# aw_801_oscilloscope.net
KiCad netlist of a schematic drawn in EAGLE
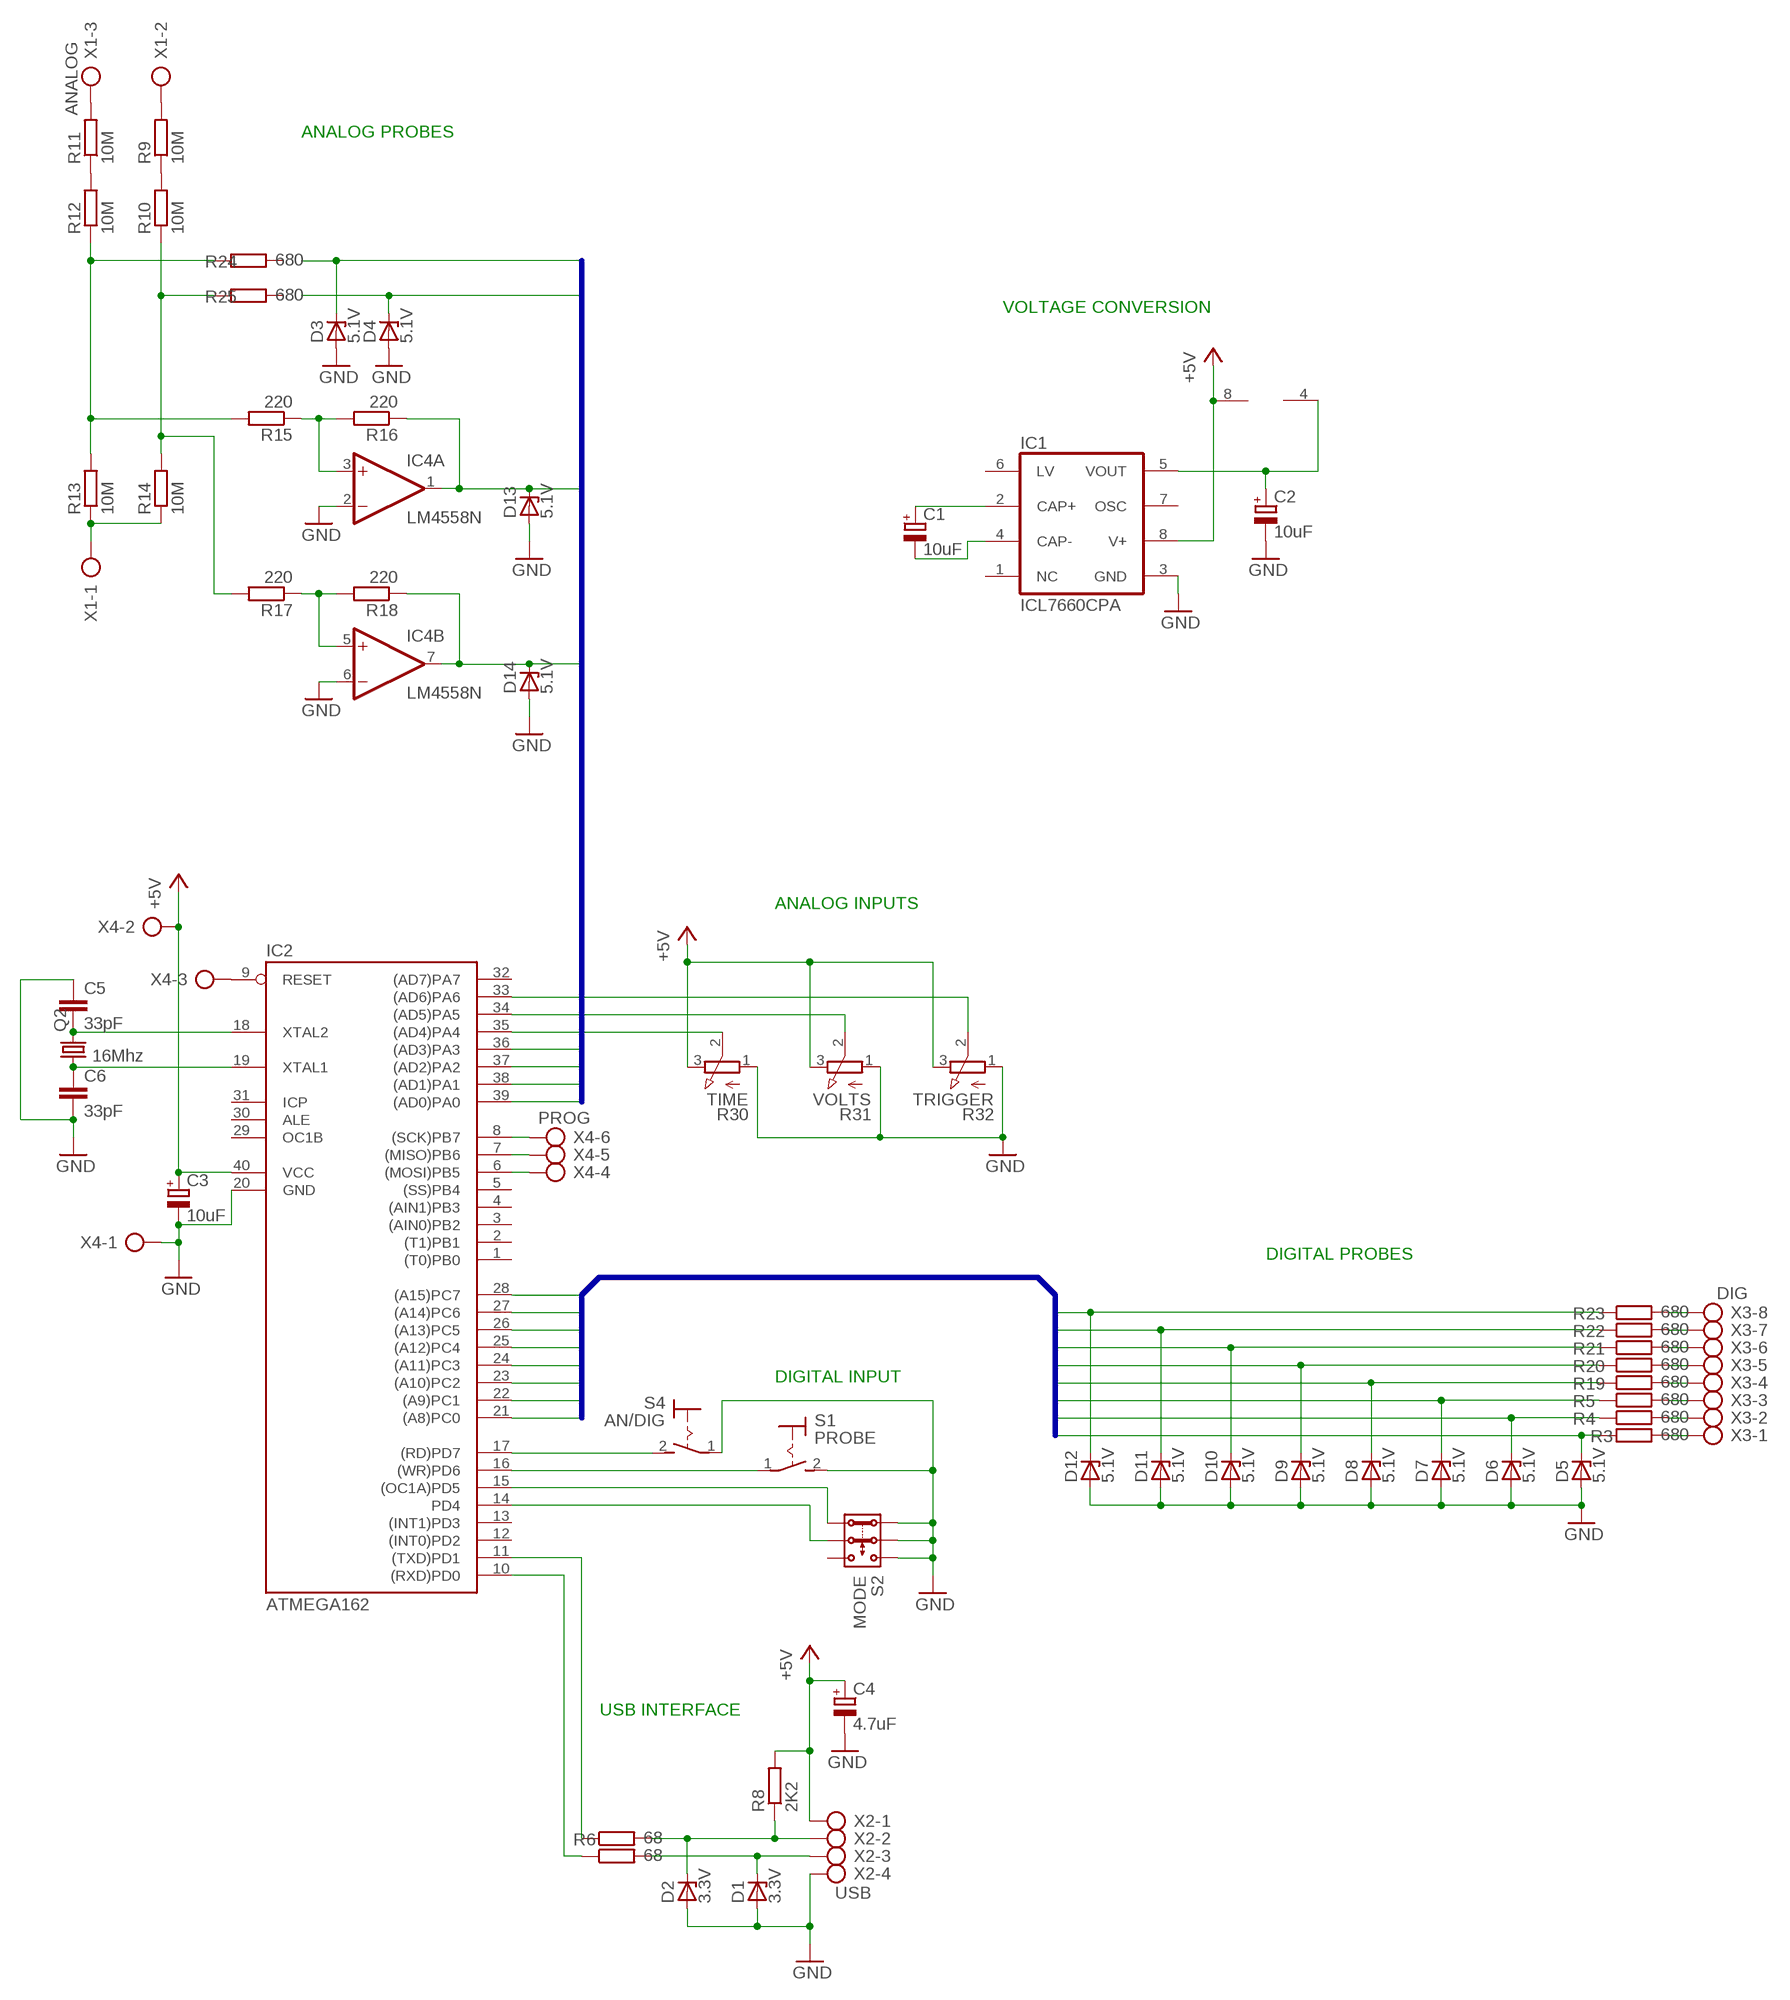
[diagram p0: schematic, sheet 1]

(export (version "E")
  (design (tool "Eeschema 10.0.6"))
  (components
    (comp (ref "C1")
      (value "10uF")
      (footprint "eagle-import:E2,5-6")
      (libsource (lib "eagle-import") (part "CPOL-EUE2.5-6"))
    )
    (comp (ref "C2")
      (value "10uF")
      (footprint "eagle-import:E2,5-6")
      (libsource (lib "eagle-import") (part "CPOL-EUE2.5-6"))
    )
    (comp (ref "C3")
      (value "10uF")
      (footprint "eagle-import:E2,5-6")
      (libsource (lib "eagle-import") (part "CPOL-EUE2.5-6"))
    )
    (comp (ref "C4")
      (value "4.7uF")
      (footprint "eagle-import:E2,5-6")
      (libsource (lib "eagle-import") (part "CPOL-EUE2.5-6"))
    )
    (comp (ref "C5")
      (value "33pF")
      (footprint "eagle-import:C050-030X075")
      (libsource (lib "eagle-import") (part "C-EU050-030X075"))
    )
    (comp (ref "C6")
      (value "33pF")
      (footprint "eagle-import:C050-030X075")
      (libsource (lib "eagle-import") (part "C-EU050-030X075"))
    )
    (comp (ref "D1")
      (value "3.3V")
      (footprint "eagle-import:DO35Z10")
      (libsource (lib "eagle-import") (part "ZENER-DIODEDO35Z10"))
    )
    (comp (ref "D2")
      (value "3.3V")
      (footprint "eagle-import:DO35Z10")
      (libsource (lib "eagle-import") (part "ZENER-DIODEDO35Z10"))
    )
    (comp (ref "D3")
      (value "5.1V")
      (footprint "eagle-import:DO35Z10")
      (libsource (lib "eagle-import") (part "ZENER-DIODEDO35Z10"))
    )
    (comp (ref "D4")
      (value "5.1V")
      (footprint "eagle-import:DO35Z10")
      (libsource (lib "eagle-import") (part "ZENER-DIODEDO35Z10"))
    )
    (comp (ref "D5")
      (value "5.1V")
      (footprint "eagle-import:DO35Z10")
      (libsource (lib "eagle-import") (part "ZENER-DIODEDO35Z10"))
    )
    (comp (ref "D6")
      (value "5.1V")
      (footprint "eagle-import:DO35Z10")
      (libsource (lib "eagle-import") (part "ZENER-DIODEDO35Z10"))
    )
    (comp (ref "D7")
      (value "5.1V")
      (footprint "eagle-import:DO35Z10")
      (libsource (lib "eagle-import") (part "ZENER-DIODEDO35Z10"))
    )
    (comp (ref "D8")
      (value "5.1V")
      (footprint "eagle-import:DO35Z10")
      (libsource (lib "eagle-import") (part "ZENER-DIODEDO35Z10"))
    )
    (comp (ref "D9")
      (value "5.1V")
      (footprint "eagle-import:DO35Z10")
      (libsource (lib "eagle-import") (part "ZENER-DIODEDO35Z10"))
    )
    (comp (ref "D10")
      (value "5.1V")
      (footprint "eagle-import:DO35Z10")
      (libsource (lib "eagle-import") (part "ZENER-DIODEDO35Z10"))
    )
    (comp (ref "D11")
      (value "5.1V")
      (footprint "eagle-import:DO35Z10")
      (libsource (lib "eagle-import") (part "ZENER-DIODEDO35Z10"))
    )
    (comp (ref "D12")
      (value "5.1V")
      (footprint "eagle-import:DO35Z10")
      (libsource (lib "eagle-import") (part "ZENER-DIODEDO35Z10"))
    )
    (comp (ref "D13")
      (value "5.1V")
      (footprint "eagle-import:DO35Z10")
      (libsource (lib "eagle-import") (part "ZENER-DIODEDO35Z10"))
    )
    (comp (ref "D14")
      (value "5.1V")
      (footprint "eagle-import:DO35Z10")
      (libsource (lib "eagle-import") (part "ZENER-DIODEDO35Z10"))
    )
    (comp (ref "IC1")
      (value "ICL7660CPA")
      (footprint "eagle-import:DIL08")
      (fields (field (name "MF") "INTERSIL"))
      (libsource (lib "eagle-import") (part "ICL7660CPA"))
    )
    (comp (ref "IC2")
      (value "ATMEGA162")
      (footprint "eagle-import:DIL40")
      (libsource (lib "eagle-import") (part "AT90S8515P"))
    )
    (comp (ref "IC4")
      (value "LM4558N")
      (footprint "eagle-import:DIL08")
      (libsource (lib "eagle-import") (part "4558NLM"))
    )
    (comp (ref "Q2")
      (value "16Mhz")
      (footprint "eagle-import:HC49U70")
      (libsource (lib "eagle-import") (part "CRYSTALHC49U70"))
    )
    (comp (ref "R3")
      (value "680")
      (footprint "eagle-import:0207_10")
      (libsource (lib "eagle-import") (part "R-EU_0207/10"))
    )
    (comp (ref "R4")
      (value "680")
      (footprint "eagle-import:0207_10")
      (libsource (lib "eagle-import") (part "R-EU_0207/10"))
    )
    (comp (ref "R5")
      (value "680")
      (footprint "eagle-import:0207_10")
      (libsource (lib "eagle-import") (part "R-EU_0207/10"))
    )
    (comp (ref "R6")
      (value "68")
      (footprint "eagle-import:0207_10")
      (libsource (lib "eagle-import") (part "R-EU_0207/10"))
    )
    (comp (ref "R7")
      (value "68")
      (footprint "eagle-import:0207_10")
      (libsource (lib "eagle-import") (part "R-EU_0207/10"))
    )
    (comp (ref "R8")
      (value "2K2")
      (footprint "eagle-import:0207_10")
      (libsource (lib "eagle-import") (part "R-EU_0207/10"))
    )
    (comp (ref "R9")
      (value "10M")
      (footprint "eagle-import:0207_10")
      (libsource (lib "eagle-import") (part "R-EU_0207/10"))
    )
    (comp (ref "R10")
      (value "10M")
      (footprint "eagle-import:0207_10")
      (libsource (lib "eagle-import") (part "R-EU_0207/10"))
    )
    (comp (ref "R11")
      (value "10M")
      (footprint "eagle-import:0207_10")
      (libsource (lib "eagle-import") (part "R-EU_0207/10"))
    )
    (comp (ref "R12")
      (value "10M")
      (footprint "eagle-import:0207_10")
      (libsource (lib "eagle-import") (part "R-EU_0207/10"))
    )
    (comp (ref "R13")
      (value "10M")
      (footprint "eagle-import:0207_10")
      (libsource (lib "eagle-import") (part "R-EU_0207/10"))
    )
    (comp (ref "R14")
      (value "10M")
      (footprint "eagle-import:0207_10")
      (libsource (lib "eagle-import") (part "R-EU_0207/10"))
    )
    (comp (ref "R15")
      (value "220")
      (footprint "eagle-import:0207_10")
      (libsource (lib "eagle-import") (part "R-EU_0207/10"))
    )
    (comp (ref "R16")
      (value "220")
      (footprint "eagle-import:0207_10")
      (libsource (lib "eagle-import") (part "R-EU_0207/10"))
    )
    (comp (ref "R17")
      (value "220")
      (footprint "eagle-import:0207_10")
      (libsource (lib "eagle-import") (part "R-EU_0207/10"))
    )
    (comp (ref "R18")
      (value "220")
      (footprint "eagle-import:0207_10")
      (libsource (lib "eagle-import") (part "R-EU_0207/10"))
    )
    (comp (ref "R19")
      (value "680")
      (footprint "eagle-import:0207_10")
      (libsource (lib "eagle-import") (part "R-EU_0207/10"))
    )
    (comp (ref "R20")
      (value "680")
      (footprint "eagle-import:0207_10")
      (libsource (lib "eagle-import") (part "R-EU_0207/10"))
    )
    (comp (ref "R21")
      (value "680")
      (footprint "eagle-import:0207_10")
      (libsource (lib "eagle-import") (part "R-EU_0207/10"))
    )
    (comp (ref "R22")
      (value "680")
      (footprint "eagle-import:0207_10")
      (libsource (lib "eagle-import") (part "R-EU_0207/10"))
    )
    (comp (ref "R23")
      (value "680")
      (footprint "eagle-import:0207_10")
      (libsource (lib "eagle-import") (part "R-EU_0207/10"))
    )
    (comp (ref "R24")
      (value "680")
      (footprint "eagle-import:0207_10")
      (libsource (lib "eagle-import") (part "R-EU_0207/10"))
    )
    (comp (ref "R25")
      (value "680")
      (footprint "eagle-import:0207_10")
      (libsource (lib "eagle-import") (part "R-EU_0207/10"))
    )
    (comp (ref "R30")
      (value "TIME")
      (footprint "eagle-import:3RP_1610N")
      (libsource (lib "eagle-import") (part "3RP/1610N"))
    )
    (comp (ref "R31")
      (value "VOLTS")
      (footprint "eagle-import:3RP_1610N")
      (libsource (lib "eagle-import") (part "3RP/1610N"))
    )
    (comp (ref "R32")
      (value "TRIGGER")
      (footprint "eagle-import:3RP_1610N")
      (libsource (lib "eagle-import") (part "3RP/1610N"))
    )
    (comp (ref "S1")
      (value "PROBE")
      (footprint "eagle-import:MS243")
      (libsource (lib "eagle-import") (part "MS243"))
    )
    (comp (ref "S2")
      (value "MODE")
      (footprint "eagle-import:2P2T")
      (libsource (lib "eagle-import") (part "2P2T"))
    )
    (comp (ref "S4")
      (value "AN/DIG")
      (footprint "eagle-import:MS243")
      (libsource (lib "eagle-import") (part "MS243"))
    )
    (comp (ref "X1")
      (value "ANALOG")
      (footprint "eagle-import:AK500_3")
      (libsource (lib "eagle-import") (part "AK500/3"))
    )
    (comp (ref "X2")
      (value "USB")
      (footprint "eagle-import:AK500_4")
      (libsource (lib "eagle-import") (part "AK500/4"))
    )
    (comp (ref "X3")
      (value "DIG")
      (footprint "eagle-import:AK500_8")
      (libsource (lib "eagle-import") (part "AK500/8"))
    )
    (comp (ref "X4")
      (value "PROG")
      (footprint "eagle-import:AK300_6")
      (libsource (lib "eagle-import") (part "AK300/6"))
    )
  )
  (nets
    (net (code "1") (name "+5V") (class "Default")
      (node (ref "C3") (pin "+") (pinfunction "+_+") (pintype "passive"))
      (node (ref "C4") (pin "+") (pinfunction "+_+") (pintype "passive"))
      (node (ref "IC1") (pin "8") (pinfunction "V+_8") (pintype "power_in"))
      (node (ref "IC2") (pin "40") (pinfunction "VCC_40") (pintype "power_in"))
      (node (ref "IC4") (pin "8") (pinfunction "V+_8") (pintype "power_in"))
      (node (ref "R30") (pin "3") (pinfunction "E_3") (pintype "passive"))
      (node (ref "R31") (pin "3") (pinfunction "E_3") (pintype "passive"))
      (node (ref "R32") (pin "3") (pinfunction "E_3") (pintype "passive"))
      (node (ref "R8") (pin "2") (pinfunction "2_2") (pintype "passive"))
      (node (ref "X2") (pin "1") (pinfunction "KL_1") (pintype "passive"))
      (node (ref "X4") (pin "2") (pinfunction "KL_2") (pintype "passive"))
    )
    (net (code "2") (name "/ANALOG0") (class "Default")
      (node (ref "D3") (pin "C") (pinfunction "C_C") (pintype "passive"))
      (node (ref "IC2") (pin "39") (pinfunction "(AD0)PA0_39") (pintype "bidirectional"))
    )
    (net (code "3") (name "/ANALOG1") (class "Default")
      (node (ref "D4") (pin "C") (pinfunction "C_C") (pintype "passive"))
      (node (ref "IC2") (pin "38") (pinfunction "(AD1)PA1_38") (pintype "bidirectional"))
    )
    (net (code "4") (name "/ANALOG2") (class "Default")
      (node (ref "D13") (pin "C") (pinfunction "C_C") (pintype "passive"))
      (node (ref "IC2") (pin "37") (pinfunction "(AD2)PA2_37") (pintype "bidirectional"))
      (node (ref "IC4") (pin "1") (pinfunction "OUT_1") (pintype "output"))
      (node (ref "R16") (pin "1") (pinfunction "1_1") (pintype "passive"))
    )
    (net (code "5") (name "/ANALOG3") (class "Default")
      (node (ref "D14") (pin "C") (pinfunction "C_C") (pintype "passive"))
      (node (ref "IC2") (pin "36") (pinfunction "(AD3)PA3_36") (pintype "bidirectional"))
      (node (ref "IC4") (pin "7") (pinfunction "OUT_7") (pintype "output"))
      (node (ref "R18") (pin "1") (pinfunction "1_1") (pintype "passive"))
    )
    (net (code "6") (name "/DIG0") (class "Default")
      (node (ref "D12") (pin "C") (pinfunction "C_C") (pintype "passive"))
      (node (ref "IC2") (pin "21") (pinfunction "(A8)PC0_21") (pintype "bidirectional"))
      (node (ref "R23") (pin "1") (pinfunction "1_1") (pintype "passive"))
    )
    (net (code "7") (name "/DIG1") (class "Default")
      (node (ref "D11") (pin "C") (pinfunction "C_C") (pintype "passive"))
      (node (ref "IC2") (pin "22") (pinfunction "(A9)PC1_22") (pintype "bidirectional"))
      (node (ref "R22") (pin "1") (pinfunction "1_1") (pintype "passive"))
    )
    (net (code "8") (name "/DIG2") (class "Default")
      (node (ref "D10") (pin "C") (pinfunction "C_C") (pintype "passive"))
      (node (ref "IC2") (pin "23") (pinfunction "(A10)PC2_23") (pintype "bidirectional"))
      (node (ref "R21") (pin "1") (pinfunction "1_1") (pintype "passive"))
    )
    (net (code "9") (name "/DIG3") (class "Default")
      (node (ref "D9") (pin "C") (pinfunction "C_C") (pintype "passive"))
      (node (ref "IC2") (pin "24") (pinfunction "(A11)PC3_24") (pintype "bidirectional"))
      (node (ref "R20") (pin "1") (pinfunction "1_1") (pintype "passive"))
    )
    (net (code "10") (name "/DIG4") (class "Default")
      (node (ref "D8") (pin "C") (pinfunction "C_C") (pintype "passive"))
      (node (ref "IC2") (pin "25") (pinfunction "(A12)PC4_25") (pintype "bidirectional"))
      (node (ref "R19") (pin "1") (pinfunction "1_1") (pintype "passive"))
    )
    (net (code "11") (name "/DIG5") (class "Default")
      (node (ref "D7") (pin "C") (pinfunction "C_C") (pintype "passive"))
      (node (ref "IC2") (pin "26") (pinfunction "(A13)PC5_26") (pintype "bidirectional"))
      (node (ref "R5") (pin "1") (pinfunction "1_1") (pintype "passive"))
    )
    (net (code "12") (name "/DIG6") (class "Default")
      (node (ref "D6") (pin "C") (pinfunction "C_C") (pintype "passive"))
      (node (ref "IC2") (pin "27") (pinfunction "(A14)PC6_27") (pintype "bidirectional"))
      (node (ref "R4") (pin "1") (pinfunction "1_1") (pintype "passive"))
    )
    (net (code "13") (name "/DIG7") (class "Default")
      (node (ref "D5") (pin "C") (pinfunction "C_C") (pintype "passive"))
      (node (ref "IC2") (pin "28") (pinfunction "(A15)PC7_28") (pintype "bidirectional"))
      (node (ref "R3") (pin "1") (pinfunction "1_1") (pintype "passive"))
    )
    (net (code "14") (name "GND") (class "Default")
      (node (ref "C2") (pin "-") (pinfunction "-_-") (pintype "passive"))
      (node (ref "C3") (pin "-") (pinfunction "-_-") (pintype "passive"))
      (node (ref "C4") (pin "-") (pinfunction "-_-") (pintype "passive"))
      (node (ref "C5") (pin "1") (pinfunction "1_1") (pintype "passive"))
      (node (ref "C6") (pin "2") (pinfunction "2_2") (pintype "passive"))
      (node (ref "D1") (pin "A") (pinfunction "A_A") (pintype "passive"))
      (node (ref "D10") (pin "A") (pinfunction "A_A") (pintype "passive"))
      (node (ref "D11") (pin "A") (pinfunction "A_A") (pintype "passive"))
      (node (ref "D12") (pin "A") (pinfunction "A_A") (pintype "passive"))
      (node (ref "D13") (pin "A") (pinfunction "A_A") (pintype "passive"))
      (node (ref "D14") (pin "A") (pinfunction "A_A") (pintype "passive"))
      (node (ref "D2") (pin "A") (pinfunction "A_A") (pintype "passive"))
      (node (ref "D3") (pin "A") (pinfunction "A_A") (pintype "passive"))
      (node (ref "D4") (pin "A") (pinfunction "A_A") (pintype "passive"))
      (node (ref "D5") (pin "A") (pinfunction "A_A") (pintype "passive"))
      (node (ref "D6") (pin "A") (pinfunction "A_A") (pintype "passive"))
      (node (ref "D7") (pin "A") (pinfunction "A_A") (pintype "passive"))
      (node (ref "D8") (pin "A") (pinfunction "A_A") (pintype "passive"))
      (node (ref "D9") (pin "A") (pinfunction "A_A") (pintype "passive"))
      (node (ref "IC1") (pin "3") (pinfunction "GND_3") (pintype "power_in"))
      (node (ref "IC2") (pin "20") (pinfunction "GND_20") (pintype "power_in"))
      (node (ref "IC4") (pin "2") (pinfunction "-IN_2") (pintype "input"))
      (node (ref "IC4") (pin "6") (pinfunction "-IN_6") (pintype "input"))
      (node (ref "R30") (pin "1") (pinfunction "A_1") (pintype "passive"))
      (node (ref "R31") (pin "1") (pinfunction "A_1") (pintype "passive"))
      (node (ref "R32") (pin "1") (pinfunction "A_1") (pintype "passive"))
      (node (ref "S1") (pin "2") (pinfunction "S_2") (pintype "passive"))
      (node (ref "S2") (pin "1.1") (pinfunction "1.1_1.1") (pintype "passive"))
      (node (ref "S2") (pin "2.1") (pinfunction "2.1_2.1") (pintype "passive"))
      (node (ref "S2") (pin "3.1") (pinfunction "3.1_3.1") (pintype "passive"))
      (node (ref "S4") (pin "1") (pinfunction "P_1") (pintype "passive"))
      (node (ref "X2") (pin "4") (pinfunction "KL_4") (pintype "passive"))
      (node (ref "X4") (pin "1") (pinfunction "KL_1") (pintype "passive"))
    )
    (net (code "15") (name "Net-(IC1-CAP+)") (class "Default")
      (node (ref "C1") (pin "+") (pinfunction "+_+") (pintype "passive"))
      (node (ref "IC1") (pin "2") (pinfunction "CAP+_2") (pintype "passive"))
    )
    (net (code "16") (name "Net-(IC1-CAP-)") (class "Default")
      (node (ref "C1") (pin "-") (pinfunction "-_-") (pintype "passive"))
      (node (ref "IC1") (pin "4") (pinfunction "CAP-_4") (pintype "passive"))
    )
    (net (code "17") (name "Net-(IC1-VOUT)") (class "Default")
      (node (ref "C2") (pin "+") (pinfunction "+_+") (pintype "passive"))
      (node (ref "IC1") (pin "5") (pinfunction "VOUT_5") (pintype "power_in"))
      (node (ref "IC4") (pin "4") (pinfunction "V-_4") (pintype "power_in"))
    )
    (net (code "18") (name "Net-(IC2-(AD4)PA4)") (class "Default")
      (node (ref "IC2") (pin "35") (pinfunction "(AD4)PA4_35") (pintype "bidirectional"))
      (node (ref "R30") (pin "2") (pinfunction "S_2") (pintype "passive"))
    )
    (net (code "19") (name "Net-(IC2-(AD5)PA5)") (class "Default")
      (node (ref "IC2") (pin "34") (pinfunction "(AD5)PA5_34") (pintype "bidirectional"))
      (node (ref "R31") (pin "2") (pinfunction "S_2") (pintype "passive"))
    )
    (net (code "20") (name "Net-(IC2-(AD6)PA6)") (class "Default")
      (node (ref "IC2") (pin "33") (pinfunction "(AD6)PA6_33") (pintype "bidirectional"))
      (node (ref "R32") (pin "2") (pinfunction "S_2") (pintype "passive"))
    )
    (net (code "21") (name "Net-(IC2-(MISO)PB6)") (class "Default")
      (node (ref "IC2") (pin "7") (pinfunction "(MISO)PB6_7") (pintype "bidirectional"))
      (node (ref "X4") (pin "5") (pinfunction "KL_5") (pintype "passive"))
    )
    (net (code "22") (name "Net-(IC2-(MOSI)PB5)") (class "Default")
      (node (ref "IC2") (pin "6") (pinfunction "(MOSI)PB5_6") (pintype "bidirectional"))
      (node (ref "X4") (pin "4") (pinfunction "KL_4") (pintype "passive"))
    )
    (net (code "23") (name "Net-(IC2-(OC1A)PD5)") (class "Default")
      (node (ref "IC2") (pin "15") (pinfunction "(OC1A)PD5_15") (pintype "bidirectional"))
      (node (ref "S2") (pin "1.2") (pinfunction "1.2_1.2") (pintype "passive"))
    )
    (net (code "24") (name "Net-(IC2-(RD)PD7)") (class "Default")
      (node (ref "IC2") (pin "17") (pinfunction "(RD)PD7_17") (pintype "bidirectional"))
      (node (ref "S4") (pin "2") (pinfunction "S_2") (pintype "passive"))
    )
    (net (code "25") (name "Net-(IC2-(RXD)PD0)") (class "Default")
      (node (ref "IC2") (pin "10") (pinfunction "(RXD)PD0_10") (pintype "bidirectional"))
      (node (ref "R7") (pin "1") (pinfunction "1_1") (pintype "passive"))
    )
    (net (code "26") (name "Net-(IC2-(SCK)PB7)") (class "Default")
      (node (ref "IC2") (pin "8") (pinfunction "(SCK)PB7_8") (pintype "bidirectional"))
      (node (ref "X4") (pin "6") (pinfunction "KL_6") (pintype "passive"))
    )
    (net (code "27") (name "Net-(IC2-(TXD)PD1)") (class "Default")
      (node (ref "IC2") (pin "11") (pinfunction "(TXD)PD1_11") (pintype "bidirectional"))
      (node (ref "R6") (pin "1") (pinfunction "1_1") (pintype "passive"))
    )
    (net (code "28") (name "Net-(IC2-(WR)PD6)") (class "Default")
      (node (ref "IC2") (pin "16") (pinfunction "(WR)PD6_16") (pintype "bidirectional"))
      (node (ref "S1") (pin "1") (pinfunction "P_1") (pintype "passive"))
    )
    (net (code "29") (name "Net-(IC2-PD4)") (class "Default")
      (node (ref "IC2") (pin "14") (pinfunction "PD4_14") (pintype "bidirectional"))
      (node (ref "S2") (pin "2.2") (pinfunction "2.2_2.2") (pintype "passive"))
    )
    (net (code "30") (name "Net-(IC2-RESET)") (class "Default")
      (node (ref "IC2") (pin "9") (pinfunction "RESET_9") (pintype "input"))
      (node (ref "X4") (pin "3") (pinfunction "KL_3") (pintype "passive"))
    )
    (net (code "31") (name "Net-(IC2-XTAL1)") (class "Default")
      (node (ref "C6") (pin "1") (pinfunction "1_1") (pintype "passive"))
      (node (ref "IC2") (pin "19") (pinfunction "XTAL1_19") (pintype "bidirectional"))
      (node (ref "Q2") (pin "1") (pinfunction "1_1") (pintype "passive"))
    )
    (net (code "32") (name "Net-(IC2-XTAL2)") (class "Default")
      (node (ref "C5") (pin "2") (pinfunction "2_2") (pintype "passive"))
      (node (ref "IC2") (pin "18") (pinfunction "XTAL2_18") (pintype "bidirectional"))
      (node (ref "Q2") (pin "2") (pinfunction "2_2") (pintype "passive"))
    )
    (net (code "33") (name "Net-(IC4A-+IN)") (class "Default")
      (node (ref "IC4") (pin "3") (pinfunction "+IN_3") (pintype "input"))
      (node (ref "R15") (pin "1") (pinfunction "1_1") (pintype "passive"))
      (node (ref "R16") (pin "2") (pinfunction "2_2") (pintype "passive"))
    )
    (net (code "34") (name "Net-(IC4B-+IN)") (class "Default")
      (node (ref "IC4") (pin "5") (pinfunction "+IN_5") (pintype "input"))
      (node (ref "R17") (pin "1") (pinfunction "1_1") (pintype "passive"))
      (node (ref "R18") (pin "2") (pinfunction "2_2") (pintype "passive"))
    )
    (net (code "35") (name "Net-(R10-Pad1)") (class "Default")
      (node (ref "R10") (pin "1") (pinfunction "1_1") (pintype "passive"))
      (node (ref "R14") (pin "2") (pinfunction "2_2") (pintype "passive"))
      (node (ref "R17") (pin "2") (pinfunction "2_2") (pintype "passive"))
      (node (ref "R25") (pin "1") (pinfunction "1_1") (pintype "passive"))
    )
    (net (code "36") (name "Net-(R10-Pad2)") (class "Default")
      (node (ref "R10") (pin "2") (pinfunction "2_2") (pintype "passive"))
      (node (ref "R9") (pin "1") (pinfunction "1_1") (pintype "passive"))
    )
    (net (code "37") (name "Net-(R11-Pad1)") (class "Default")
      (node (ref "R11") (pin "1") (pinfunction "1_1") (pintype "passive"))
      (node (ref "R12") (pin "2") (pinfunction "2_2") (pintype "passive"))
    )
    (net (code "38") (name "Net-(R12-Pad1)") (class "Default")
      (node (ref "R12") (pin "1") (pinfunction "1_1") (pintype "passive"))
      (node (ref "R13") (pin "2") (pinfunction "2_2") (pintype "passive"))
      (node (ref "R15") (pin "2") (pinfunction "2_2") (pintype "passive"))
      (node (ref "R24") (pin "1") (pinfunction "1_1") (pintype "passive"))
    )
    (net (code "39") (name "Net-(X1A-KL)") (class "Default")
      (node (ref "R13") (pin "1") (pinfunction "1_1") (pintype "passive"))
      (node (ref "R14") (pin "1") (pinfunction "1_1") (pintype "passive"))
      (node (ref "X1") (pin "1") (pinfunction "KL_1") (pintype "passive"))
    )
    (net (code "40") (name "Net-(X1B-KL)") (class "Default")
      (node (ref "R9") (pin "2") (pinfunction "2_2") (pintype "passive"))
      (node (ref "X1") (pin "2") (pinfunction "KL_2") (pintype "passive"))
    )
    (net (code "41") (name "Net-(X1C-KL)") (class "Default")
      (node (ref "R11") (pin "2") (pinfunction "2_2") (pintype "passive"))
      (node (ref "X1") (pin "3") (pinfunction "KL_3") (pintype "passive"))
    )
    (net (code "42") (name "Net-(X2B-KL)") (class "Default")
      (node (ref "D2") (pin "C") (pinfunction "C_C") (pintype "passive"))
      (node (ref "R6") (pin "2") (pinfunction "2_2") (pintype "passive"))
      (node (ref "R8") (pin "1") (pinfunction "1_1") (pintype "passive"))
      (node (ref "X2") (pin "2") (pinfunction "KL_2") (pintype "passive"))
    )
    (net (code "43") (name "Net-(X2C-KL)") (class "Default")
      (node (ref "D1") (pin "C") (pinfunction "C_C") (pintype "passive"))
      (node (ref "R7") (pin "2") (pinfunction "2_2") (pintype "passive"))
      (node (ref "X2") (pin "3") (pinfunction "KL_3") (pintype "passive"))
    )
    (net (code "44") (name "Net-(X3A-KL)") (class "Default")
      (node (ref "R3") (pin "2") (pinfunction "2_2") (pintype "passive"))
      (node (ref "X3") (pin "1") (pinfunction "KL_1") (pintype "passive"))
    )
    (net (code "45") (name "Net-(X3B-KL)") (class "Default")
      (node (ref "R4") (pin "2") (pinfunction "2_2") (pintype "passive"))
      (node (ref "X3") (pin "2") (pinfunction "KL_2") (pintype "passive"))
    )
    (net (code "46") (name "Net-(X3C-KL)") (class "Default")
      (node (ref "R5") (pin "2") (pinfunction "2_2") (pintype "passive"))
      (node (ref "X3") (pin "3") (pinfunction "KL_3") (pintype "passive"))
    )
    (net (code "47") (name "Net-(X3D-KL)") (class "Default")
      (node (ref "R19") (pin "2") (pinfunction "2_2") (pintype "passive"))
      (node (ref "X3") (pin "4") (pinfunction "KL_4") (pintype "passive"))
    )
    (net (code "48") (name "Net-(X3E-KL)") (class "Default")
      (node (ref "R20") (pin "2") (pinfunction "2_2") (pintype "passive"))
      (node (ref "X3") (pin "5") (pinfunction "KL_5") (pintype "passive"))
    )
    (net (code "49") (name "Net-(X3F-KL)") (class "Default")
      (node (ref "R21") (pin "2") (pinfunction "2_2") (pintype "passive"))
      (node (ref "X3") (pin "6") (pinfunction "KL_6") (pintype "passive"))
    )
    (net (code "50") (name "Net-(X3G-KL)") (class "Default")
      (node (ref "R22") (pin "2") (pinfunction "2_2") (pintype "passive"))
      (node (ref "X3") (pin "7") (pinfunction "KL_7") (pintype "passive"))
    )
    (net (code "51") (name "Net-(X3H-KL)") (class "Default")
      (node (ref "R23") (pin "2") (pinfunction "2_2") (pintype "passive"))
      (node (ref "X3") (pin "8") (pinfunction "KL_8") (pintype "passive"))
    )
    (net (code "52") (name "unconnected-(IC1-LV-Pad6)") (class "Default")
      (node (ref "IC1") (pin "6") (pinfunction "LV_6") (pintype "passive"))
    )
    (net (code "53") (name "unconnected-(IC1-NC-Pad1)") (class "Default")
      (node (ref "IC1") (pin "1") (pinfunction "NC_1") (pintype "no_connect"))
    )
    (net (code "54") (name "unconnected-(IC1-OSC-Pad7)") (class "Default")
      (node (ref "IC1") (pin "7") (pinfunction "OSC_7") (pintype "output"))
    )
    (net (code "55") (name "unconnected-(IC2-(AD7)PA7-Pad32)") (class "Default")
      (node (ref "IC2") (pin "32") (pinfunction "(AD7)PA7_32") (pintype "bidirectional"))
    )
    (net (code "56") (name "unconnected-(IC2-(AIN0)PB2-Pad3)") (class "Default")
      (node (ref "IC2") (pin "3") (pinfunction "(AIN0)PB2_3") (pintype "bidirectional"))
    )
    (net (code "57") (name "unconnected-(IC2-(AIN1)PB3-Pad4)") (class "Default")
      (node (ref "IC2") (pin "4") (pinfunction "(AIN1)PB3_4") (pintype "bidirectional"))
    )
    (net (code "58") (name "unconnected-(IC2-(INT0)PD2-Pad12)") (class "Default")
      (node (ref "IC2") (pin "12") (pinfunction "(INT0)PD2_12") (pintype "bidirectional"))
    )
    (net (code "59") (name "unconnected-(IC2-(INT1)PD3-Pad13)") (class "Default")
      (node (ref "IC2") (pin "13") (pinfunction "(INT1)PD3_13") (pintype "bidirectional"))
    )
    (net (code "60") (name "unconnected-(IC2-(SS)PB4-Pad5)") (class "Default")
      (node (ref "IC2") (pin "5") (pinfunction "(SS)PB4_5") (pintype "bidirectional"))
    )
    (net (code "61") (name "unconnected-(IC2-(T0)PB0-Pad1)") (class "Default")
      (node (ref "IC2") (pin "1") (pinfunction "(T0)PB0_1") (pintype "bidirectional"))
    )
    (net (code "62") (name "unconnected-(IC2-(T1)PB1-Pad2)") (class "Default")
      (node (ref "IC2") (pin "2") (pinfunction "(T1)PB1_2") (pintype "bidirectional"))
    )
    (net (code "63") (name "unconnected-(IC2-ALE-Pad30)") (class "Default")
      (node (ref "IC2") (pin "30") (pinfunction "ALE_30") (pintype "bidirectional"))
    )
    (net (code "64") (name "unconnected-(IC2-ICP-Pad31)") (class "Default")
      (node (ref "IC2") (pin "31") (pinfunction "ICP_31") (pintype "bidirectional"))
    )
    (net (code "65") (name "unconnected-(IC2-OC1B-Pad29)") (class "Default")
      (node (ref "IC2") (pin "29") (pinfunction "OC1B_29") (pintype "bidirectional"))
    )
    (net (code "66") (name "unconnected-(R24-Pad2)") (class "Default")
      (node (ref "R24") (pin "2") (pinfunction "2_2") (pintype "passive"))
    )
    (net (code "67") (name "unconnected-(R25-Pad2)") (class "Default")
      (node (ref "R25") (pin "2") (pinfunction "2_2") (pintype "passive"))
    )
    (net (code "68") (name "unconnected-(S2-Pad3.2)") (class "Default")
      (node (ref "S2") (pin "3.2") (pinfunction "3.2_3.2") (pintype "passive"))
    )
  )
)
